# ADIS_Teensy_Arduino_Breakout_RevB.net
KiCad netlist of a schematic drawn in EAGLE
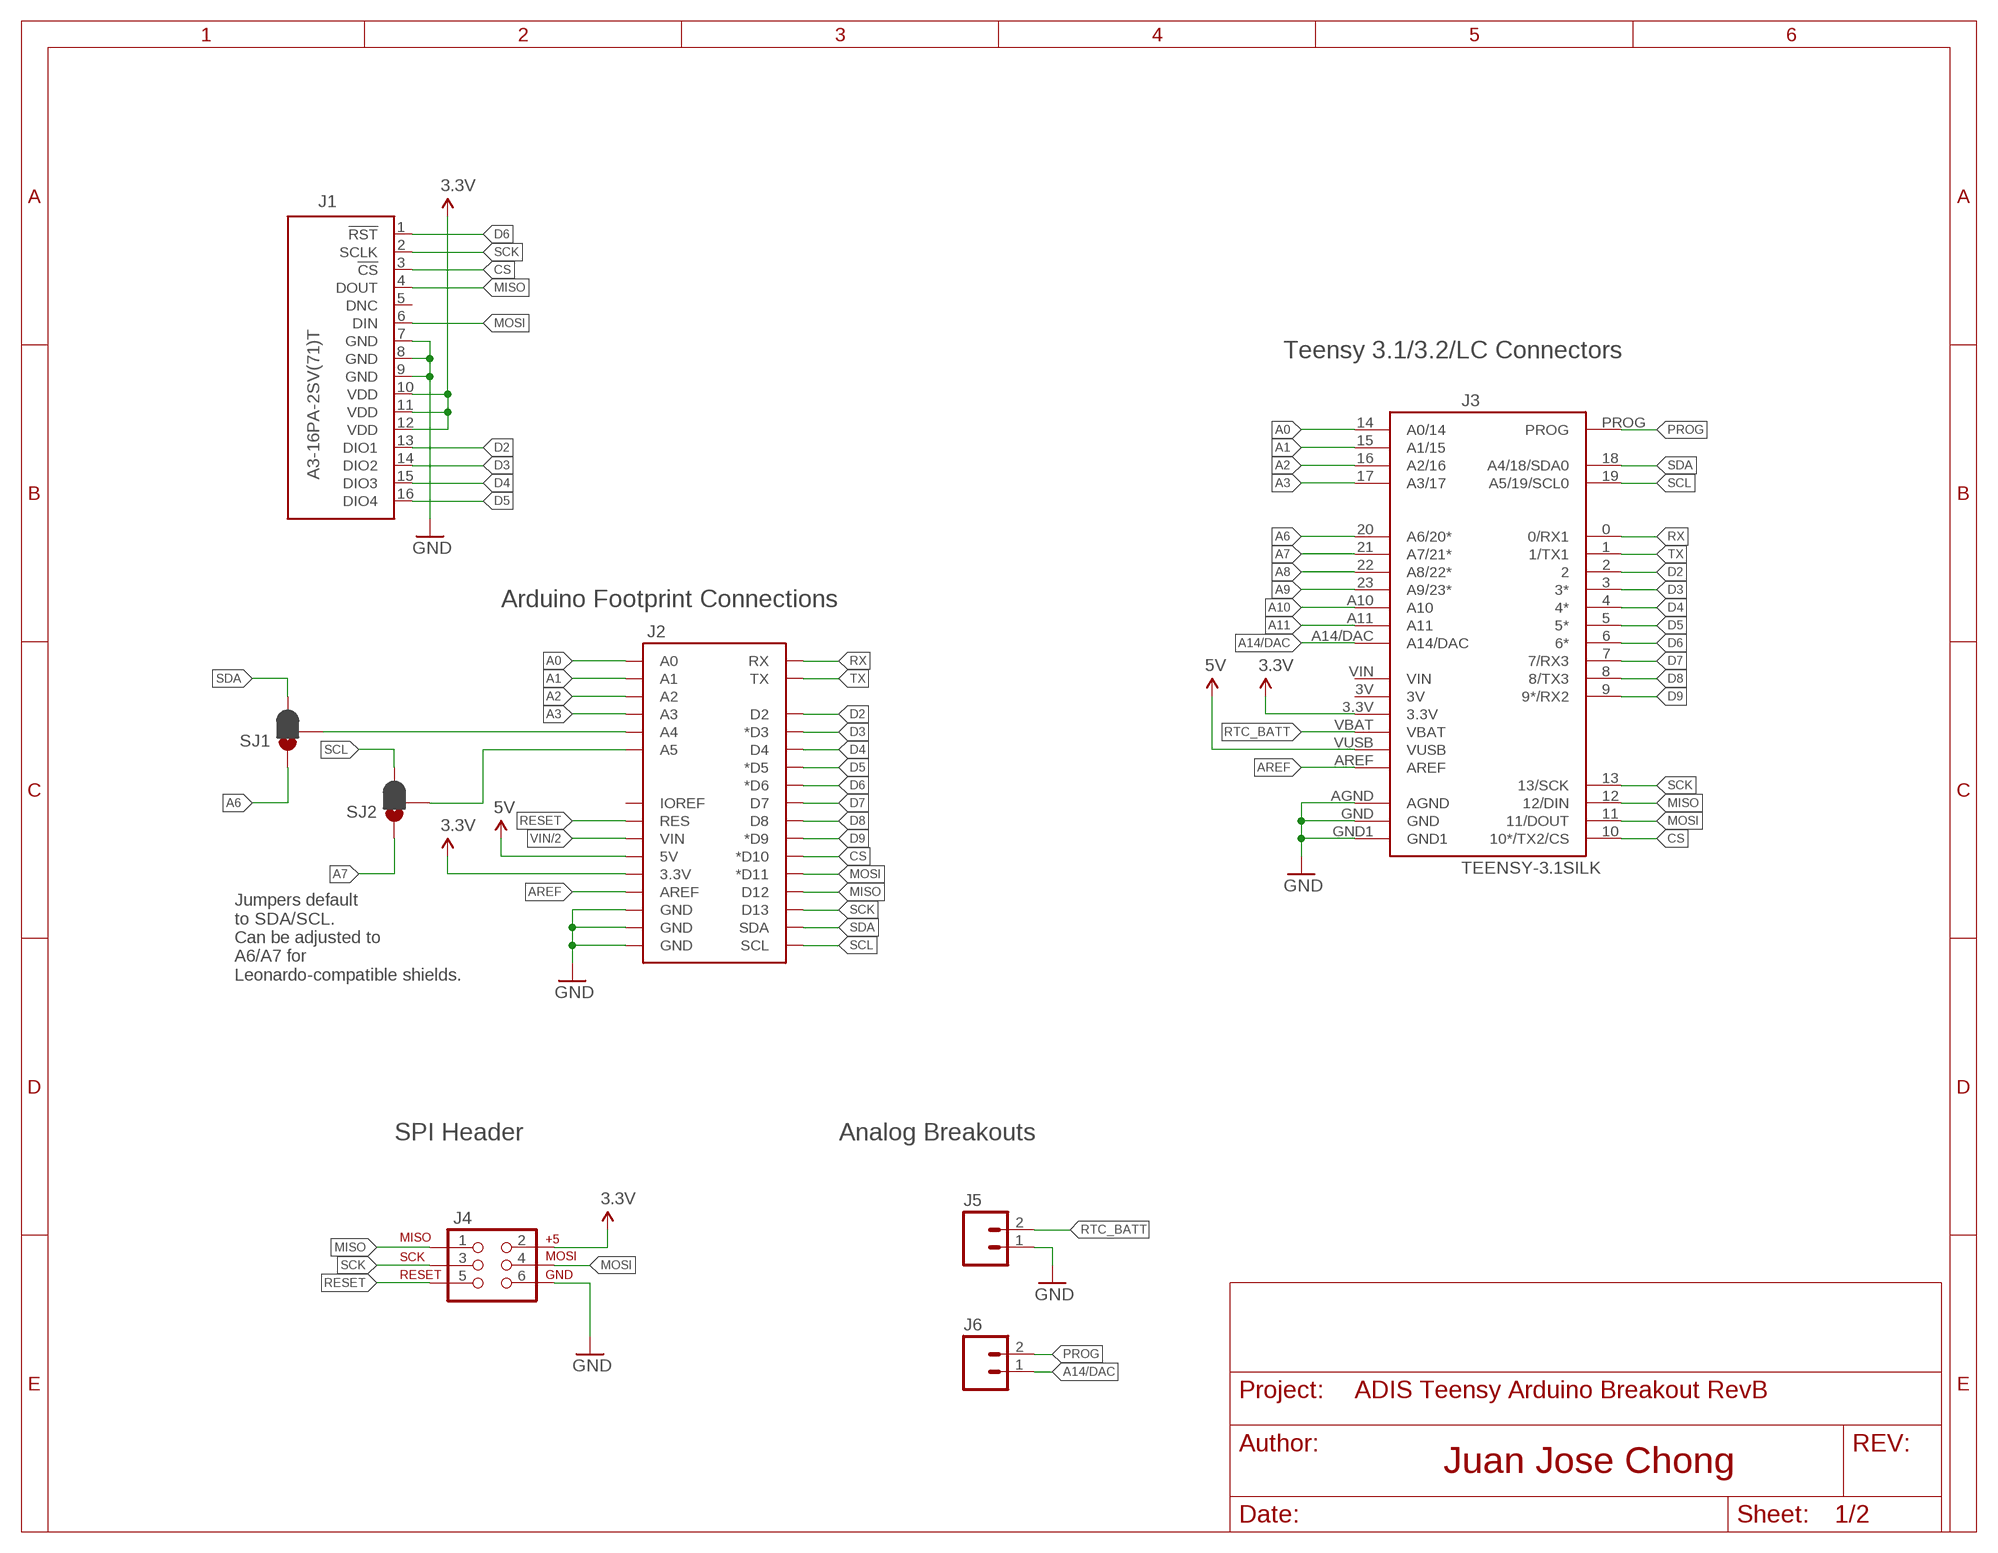
[diagram p0: schematic, sheet 1]
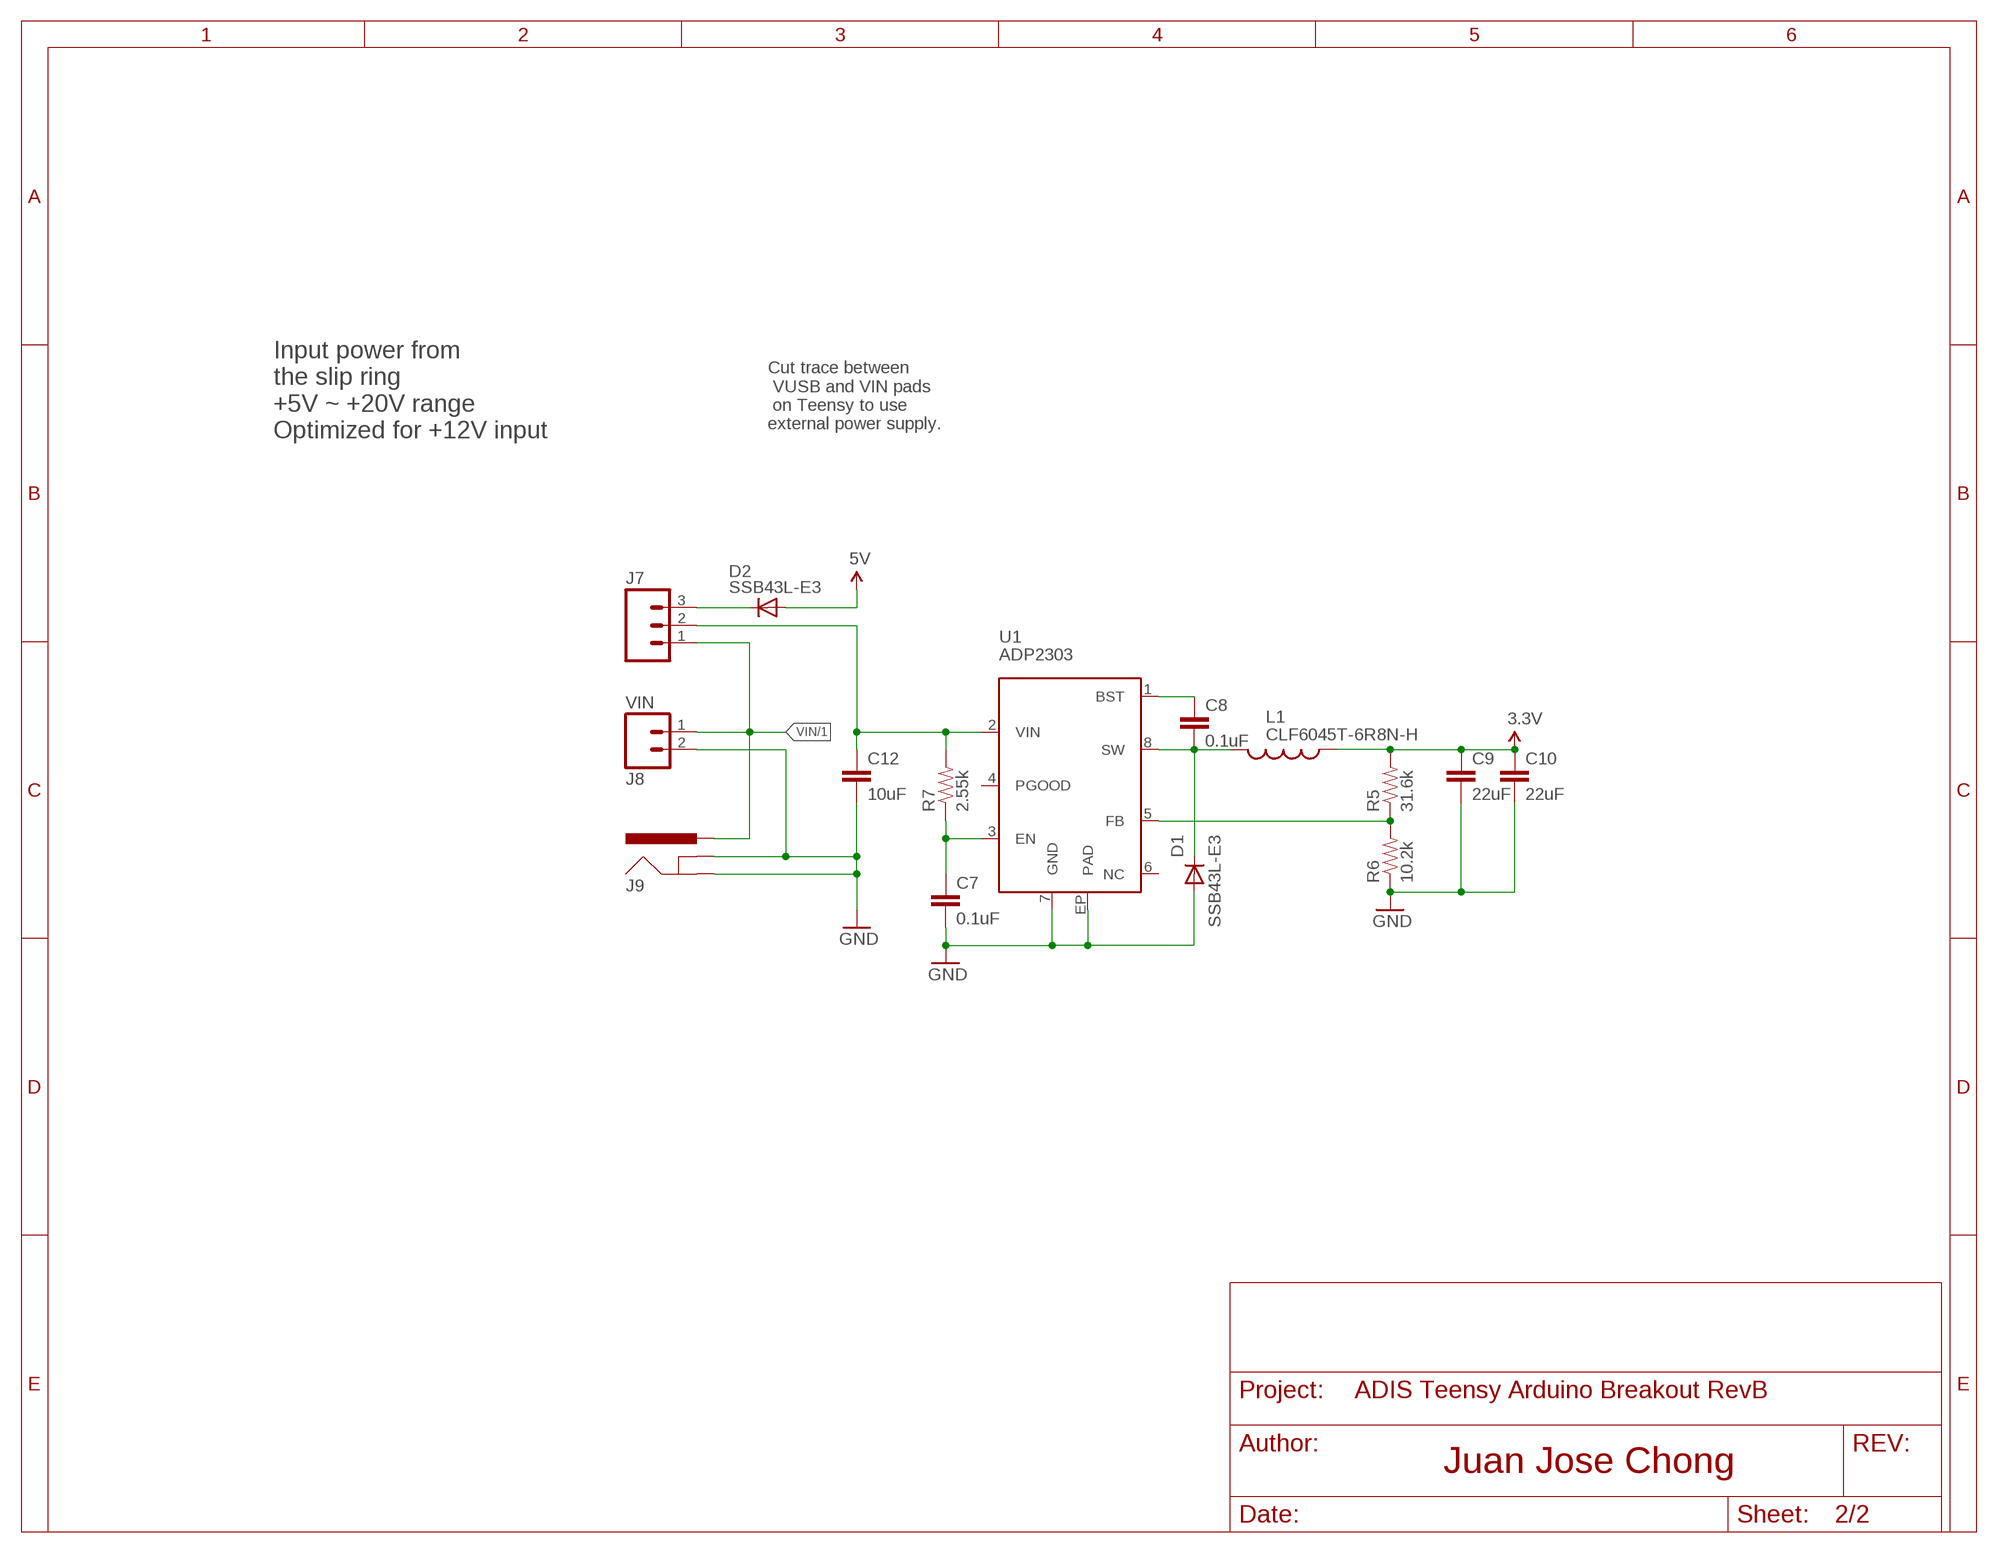
[diagram p1: schematic, sheet 2]

(export (version "E")
  (design (tool "Eeschema 10.0.6"))
  (components
    (comp (ref "C7")
      (value "0.1uF")
      (footprint "eagle-import:0603-CAP")
      (fields (field (name "PARTNO") "CL10B104KB8NNNC"))
      (libsource (lib "eagle-import") (part "CAP0603-CAP"))
    )
    (comp (ref "C8")
      (value "0.1uF")
      (footprint "eagle-import:0603-CAP")
      (fields (field (name "PARTNO") "CL10B104KB8NNNC"))
      (libsource (lib "eagle-import") (part "CAP0603-CAP"))
    )
    (comp (ref "C9")
      (value "22uF")
      (footprint "eagle-import:1210")
      (fields (field (name "PARTNO") "TLJA476M010R0600"))
      (libsource (lib "eagle-import") (part "CAP1210"))
    )
    (comp (ref "C10")
      (value "22uF")
      (footprint "eagle-import:1210")
      (fields (field (name "PARTNO") "TLJA476M010R0600"))
      (libsource (lib "eagle-import") (part "CAP1210"))
    )
    (comp (ref "C12")
      (value "10uF")
      (footprint "eagle-import:1206")
      (fields (field (name "PARTNO") "TLJA476M010R0600"))
      (libsource (lib "eagle-import") (part "CAP1206"))
    )
    (comp (ref "D1")
      (value "SSB43L-E3")
      (footprint "eagle-import:DO214AA")
      (fields (field (name "PARTNO") "SSB43L-E3/52T"))
      (libsource (lib "eagle-import") (part "DIODE-DO214AA"))
    )
    (comp (ref "D2")
      (value "SSB43L-E3")
      (footprint "eagle-import:DO214AA")
      (fields (field (name "PARTNO") "SSB43L-E3/52T"))
      (libsource (lib "eagle-import") (part "DIODE-DO214AA"))
    )
    (comp (ref "J7")
      (value "M03PTH")
      (footprint "eagle-import:1X03")
      (libsource (lib "eagle-import") (part "M03PTH"))
    )
    (comp (ref "J8")
      (value "VIN")
      (footprint "eagle-import:SCREWTERMINAL-3.5MM-2")
      (fields (field (name "PARTNO") "20020327-C021B01LF"))
      (libsource (lib "eagle-import") (part "M023.5MM"))
    )
    (comp (ref "J9")
      (value "POWER_JACKPTH_LOCK")
      (footprint "eagle-import:POWER_JACK_PTH_LOCK")
      (libsource (lib "eagle-import") (part "POWER_JACKPTH_LOCK"))
    )
    (comp (ref "L1")
      (value "CLF6045T-6R8N-H")
      (footprint "eagle-import:CLF6045-H")
      (libsource (lib "eagle-import") (part "CLF6045T-6R8N-H"))
    )
    (comp (ref "R5")
      (value "31.6k")
      (footprint "eagle-import:0603-RES")
      (fields (field (name "PARTNO") "ERJ-3EKF3162V"))
      (libsource (lib "eagle-import") (part "RESISTOR0603-RES"))
    )
    (comp (ref "R6")
      (value "10.2k")
      (footprint "eagle-import:0603-RES")
      (fields (field (name "PARTNO") "ERJ-3EKF1022V"))
      (libsource (lib "eagle-import") (part "RESISTOR0603-RES"))
    )
    (comp (ref "R7")
      (value "2.55k")
      (footprint "eagle-import:0603-RES")
      (fields (field (name "PARTNO") "ERJ-3EKF2551V"))
      (libsource (lib "eagle-import") (part "RESISTOR0603-RES"))
    )
    (comp (ref "U1")
      (value "ADP2303")
      (footprint "eagle-import:SOIC-8-PAD")
      (fields (field (name "PARTNO") "ADP2303ARDZ"))
      (libsource (lib "eagle-import") (part "ADP2303"))
    )
    (comp (ref "J1")
      (value "A3-16PA-2SV(71)T")
      (footprint "eagle-import:A3-16PA-2SV(71)-TOP")
      (libsource (lib "eagle-import") (part "A3-16PA-2SV(71)T"))
    )
    (comp (ref "J2")
      (value "ARDUINO_R3_SHIELDUNO_R3_SHIELD_HOLES")
      (footprint "eagle-import:UNO_R3_SHIELD_HOLES")
      (libsource (lib "eagle-import") (part "ARDUINO_R3_SHIELDUNO_R3_SHIELD_HOLES"))
    )
    (comp (ref "J3")
      (value "TEENSY-3.1SILK")
      (footprint "eagle-import:TEENSY-3.1")
      (libsource (lib "eagle-import") (part "TEENSY-3.1SILK"))
    )
    (comp (ref "J4")
      (value "AVR_SPI_PRG_6PTH")
      (footprint "eagle-import:2X3")
      (libsource (lib "eagle-import") (part "AVR_SPI_PRG_6PTH"))
    )
    (comp (ref "J5")
      (value "M02PTH")
      (footprint "eagle-import:1X02")
      (libsource (lib "eagle-import") (part "M02PTH"))
    )
    (comp (ref "J6")
      (value "M02PTH")
      (footprint "eagle-import:1X02")
      (libsource (lib "eagle-import") (part "M02PTH"))
    )
    (comp (ref "SJ1")
      (value "JUMPER-PAD-3-2OF3_NC_BY_PASTE")
      (footprint "eagle-import:PAD-JUMPER-3-2OF3_NC_BY_PASTE_YES_SILK_FULL_BOX")
      (libsource (lib "eagle-import") (part "JUMPER-PAD-3-2OF3_NC_BY_PASTE"))
    )
    (comp (ref "SJ2")
      (value "JUMPER-PAD-3-2OF3_NC_BY_PASTE")
      (footprint "eagle-import:PAD-JUMPER-3-2OF3_NC_BY_PASTE_YES_SILK_FULL_BOX")
      (libsource (lib "eagle-import") (part "JUMPER-PAD-3-2OF3_NC_BY_PASTE"))
    )
  )
  (nets
    (net (code "1") (name "3.3V") (class "Default")
      (node (ref "C10") (pin "1") (pinfunction "1_1") (pintype "passive"))
      (node (ref "C9") (pin "1") (pinfunction "1_1") (pintype "passive"))
      (node (ref "J1") (pin "10") (pinfunction "VDD_10") (pintype "bidirectional"))
      (node (ref "J1") (pin "11") (pinfunction "VDD_11") (pintype "bidirectional"))
      (node (ref "J1") (pin "12") (pinfunction "VDD_12") (pintype "bidirectional"))
      (node (ref "J2") (pin "3.3V") (pinfunction "3.3V_3.3V") (pintype "bidirectional"))
      (node (ref "J3") (pin "3.3V") (pinfunction "3.3V_3.3V") (pintype "bidirectional"))
      (node (ref "J4") (pin "2") (pinfunction "2_2") (pintype "passive"))
      (node (ref "L1") (pin "P$1") (pinfunction "1_P$1") (pintype "passive"))
      (node (ref "R5") (pin "2") (pinfunction "2_2") (pintype "passive"))
    )
    (net (code "2") (name "5V") (class "Default")
      (node (ref "D2") (pin "A") (pinfunction "A_A") (pintype "passive"))
      (node (ref "J2") (pin "5V") (pinfunction "5V_5V") (pintype "bidirectional"))
      (node (ref "J3") (pin "VUSB") (pinfunction "VUSB_VUSB") (pintype "bidirectional"))
    )
    (net (code "3") (name "A0") (class "Default")
      (node (ref "J2") (pin "A0") (pinfunction "A0_A0") (pintype "bidirectional"))
      (node (ref "J3") (pin "14") (pinfunction "A0/14_14") (pintype "bidirectional"))
    )
    (net (code "4") (name "A1") (class "Default")
      (node (ref "J2") (pin "A1") (pinfunction "A1_A1") (pintype "bidirectional"))
      (node (ref "J3") (pin "15") (pinfunction "A1/15_15") (pintype "bidirectional"))
    )
    (net (code "5") (name "A2") (class "Default")
      (node (ref "J2") (pin "A2") (pinfunction "A2_A2") (pintype "bidirectional"))
      (node (ref "J3") (pin "16") (pinfunction "A2/16_16") (pintype "bidirectional"))
    )
    (net (code "6") (name "A3") (class "Default")
      (node (ref "J2") (pin "A3") (pinfunction "A3_A3") (pintype "bidirectional"))
      (node (ref "J3") (pin "17") (pinfunction "A3/17_17") (pintype "bidirectional"))
    )
    (net (code "7") (name "A6") (class "Default")
      (node (ref "J3") (pin "20") (pinfunction "A6/20*_20") (pintype "bidirectional"))
      (node (ref "SJ1") (pin "1") (pinfunction "1_1") (pintype "passive"))
    )
    (net (code "8") (name "A7") (class "Default")
      (node (ref "J3") (pin "21") (pinfunction "A7/21*_21") (pintype "bidirectional"))
      (node (ref "SJ2") (pin "1") (pinfunction "1_1") (pintype "passive"))
    )
    (net (code "9") (name "A8") (class "Default")
      (node (ref "J3") (pin "22") (pinfunction "A8/22*_22") (pintype "bidirectional"))
    )
    (net (code "10") (name "A9") (class "Default")
      (node (ref "J3") (pin "23") (pinfunction "A9/23*_23") (pintype "bidirectional"))
    )
    (net (code "11") (name "A10") (class "Default")
      (node (ref "J3") (pin "A10") (pinfunction "A10_A10") (pintype "bidirectional"))
    )
    (net (code "12") (name "A11") (class "Default")
      (node (ref "J3") (pin "A11") (pinfunction "A11_A11") (pintype "bidirectional"))
    )
    (net (code "13") (name "A14{slash}DAC") (class "Default")
      (node (ref "J3") (pin "A14/DAC") (pinfunction "A14/DAC_A14/DAC") (pintype "bidirectional"))
      (node (ref "J6") (pin "1") (pinfunction "1_1") (pintype "passive"))
    )
    (net (code "14") (name "AREF") (class "Default")
      (node (ref "J2") (pin "AREF") (pinfunction "AREF_AREF") (pintype "bidirectional"))
      (node (ref "J3") (pin "AREF") (pinfunction "AREF_AREF") (pintype "bidirectional"))
    )
    (net (code "15") (name "CS") (class "Default")
      (node (ref "J1") (pin "3") (pinfunction "~{CS}_3") (pintype "bidirectional"))
      (node (ref "J2") (pin "D10") (pinfunction "*D10_D10") (pintype "bidirectional"))
      (node (ref "J3") (pin "10") (pinfunction "10*/TX2/CS_10") (pintype "bidirectional"))
    )
    (net (code "16") (name "D2") (class "Default")
      (node (ref "J1") (pin "13") (pinfunction "DIO1_13") (pintype "bidirectional"))
      (node (ref "J2") (pin "D2") (pinfunction "D2_D2") (pintype "bidirectional"))
      (node (ref "J3") (pin "2") (pinfunction "2_2") (pintype "bidirectional"))
    )
    (net (code "17") (name "D3") (class "Default")
      (node (ref "J1") (pin "14") (pinfunction "DIO2_14") (pintype "bidirectional"))
      (node (ref "J2") (pin "D3") (pinfunction "*D3_D3") (pintype "bidirectional"))
      (node (ref "J3") (pin "3") (pinfunction "3*_3") (pintype "bidirectional"))
    )
    (net (code "18") (name "D4") (class "Default")
      (node (ref "J1") (pin "15") (pinfunction "DIO3_15") (pintype "bidirectional"))
      (node (ref "J2") (pin "D4") (pinfunction "D4_D4") (pintype "bidirectional"))
      (node (ref "J3") (pin "4") (pinfunction "4*_4") (pintype "bidirectional"))
    )
    (net (code "19") (name "D5") (class "Default")
      (node (ref "J1") (pin "16") (pinfunction "DIO4_16") (pintype "bidirectional"))
      (node (ref "J2") (pin "D5") (pinfunction "*D5_D5") (pintype "bidirectional"))
      (node (ref "J3") (pin "5") (pinfunction "5*_5") (pintype "bidirectional"))
    )
    (net (code "20") (name "D6") (class "Default")
      (node (ref "J1") (pin "1") (pinfunction "~{RST}_1") (pintype "bidirectional"))
      (node (ref "J2") (pin "D6") (pinfunction "*D6_D6") (pintype "bidirectional"))
      (node (ref "J3") (pin "6") (pinfunction "6*_6") (pintype "bidirectional"))
    )
    (net (code "21") (name "D7") (class "Default")
      (node (ref "J2") (pin "D7") (pinfunction "D7_D7") (pintype "bidirectional"))
      (node (ref "J3") (pin "7") (pinfunction "7/RX3_7") (pintype "bidirectional"))
    )
    (net (code "22") (name "D8") (class "Default")
      (node (ref "J2") (pin "D8") (pinfunction "D8_D8") (pintype "bidirectional"))
      (node (ref "J3") (pin "8") (pinfunction "8/TX3_8") (pintype "bidirectional"))
    )
    (net (code "23") (name "D9") (class "Default")
      (node (ref "J2") (pin "D9") (pinfunction "*D9_D9") (pintype "bidirectional"))
      (node (ref "J3") (pin "9") (pinfunction "9*/RX2_9") (pintype "bidirectional"))
    )
    (net (code "24") (name "GND") (class "Default")
      (node (ref "C10") (pin "2") (pinfunction "2_2") (pintype "passive"))
      (node (ref "C12") (pin "2") (pinfunction "2_2") (pintype "passive"))
      (node (ref "C7") (pin "2") (pinfunction "2_2") (pintype "passive"))
      (node (ref "C9") (pin "2") (pinfunction "2_2") (pintype "passive"))
      (node (ref "D1") (pin "A") (pinfunction "A_A") (pintype "passive"))
      (node (ref "J1") (pin "7") (pinfunction "GND_7") (pintype "bidirectional"))
      (node (ref "J1") (pin "8") (pinfunction "GND_8") (pintype "bidirectional"))
      (node (ref "J1") (pin "9") (pinfunction "GND_9") (pintype "bidirectional"))
      (node (ref "J2") (pin "GND@0") (pinfunction "GND_GND@0") (pintype "bidirectional"))
      (node (ref "J2") (pin "GND@1") (pinfunction "GND_GND@1") (pintype "bidirectional"))
      (node (ref "J2") (pin "GND@2") (pinfunction "GND_GND@2") (pintype "bidirectional"))
      (node (ref "J3") (pin "AGND") (pinfunction "AGND_AGND") (pintype "bidirectional"))
      (node (ref "J3") (pin "GND") (pinfunction "GND_GND") (pintype "bidirectional"))
      (node (ref "J3") (pin "GND1") (pinfunction "GND1_GND1") (pintype "bidirectional"))
      (node (ref "J4") (pin "6") (pinfunction "6_6") (pintype "passive"))
      (node (ref "J5") (pin "1") (pinfunction "1_1") (pintype "passive"))
      (node (ref "J8") (pin "2") (pinfunction "2_2") (pintype "passive"))
      (node (ref "J9") (pin "GND") (pinfunction "GND_GND") (pintype "bidirectional"))
      (node (ref "J9") (pin "GNDBREAK") (pinfunction "GNDBREAK_GNDBREAK") (pintype "bidirectional"))
      (node (ref "R6") (pin "1") (pinfunction "1_1") (pintype "passive"))
      (node (ref "U1") (pin "7") (pinfunction "GND_7") (pintype "bidirectional"))
      (node (ref "U1") (pin "EP") (pinfunction "PAD_EP") (pintype "bidirectional"))
    )
    (net (code "25") (name "MISO") (class "Default")
      (node (ref "J1") (pin "4") (pinfunction "DOUT_4") (pintype "bidirectional"))
      (node (ref "J2") (pin "D12") (pinfunction "D12_D12") (pintype "bidirectional"))
      (node (ref "J3") (pin "12") (pinfunction "12/DIN_12") (pintype "bidirectional"))
      (node (ref "J4") (pin "1") (pinfunction "1_1") (pintype "passive"))
    )
    (net (code "26") (name "MOSI") (class "Default")
      (node (ref "J1") (pin "6") (pinfunction "DIN_6") (pintype "bidirectional"))
      (node (ref "J2") (pin "D11") (pinfunction "*D11_D11") (pintype "bidirectional"))
      (node (ref "J3") (pin "11") (pinfunction "11/DOUT_11") (pintype "bidirectional"))
      (node (ref "J4") (pin "4") (pinfunction "4_4") (pintype "passive"))
    )
    (net (code "27") (name "Net-(D2-PadC)") (class "Default")
      (node (ref "D2") (pin "C") (pinfunction "C_C") (pintype "passive"))
      (node (ref "J7") (pin "3") (pinfunction "3_3") (pintype "passive"))
    )
    (net (code "28") (name "Net-(J2-PadA4)") (class "Default")
      (node (ref "J2") (pin "A4") (pinfunction "A4_A4") (pintype "bidirectional"))
      (node (ref "SJ1") (pin "2") (pinfunction "2_2") (pintype "passive"))
    )
    (net (code "29") (name "Net-(J2-PadA5)") (class "Default")
      (node (ref "J2") (pin "A5") (pinfunction "A5_A5") (pintype "bidirectional"))
      (node (ref "SJ2") (pin "2") (pinfunction "2_2") (pintype "passive"))
    )
    (net (code "30") (name "Net-(L1-2)") (class "Default")
      (node (ref "C8") (pin "2") (pinfunction "2_2") (pintype "passive"))
      (node (ref "D1") (pin "C") (pinfunction "C_C") (pintype "passive"))
      (node (ref "L1") (pin "P$2") (pinfunction "2_P$2") (pintype "passive"))
      (node (ref "U1") (pin "8") (pinfunction "SW_8") (pintype "bidirectional"))
    )
    (net (code "31") (name "Net-(U1-BST)") (class "Default")
      (node (ref "C8") (pin "1") (pinfunction "1_1") (pintype "passive"))
      (node (ref "U1") (pin "1") (pinfunction "BST_1") (pintype "bidirectional"))
    )
    (net (code "32") (name "Net-(U1-EN)") (class "Default")
      (node (ref "C7") (pin "1") (pinfunction "1_1") (pintype "passive"))
      (node (ref "R7") (pin "1") (pinfunction "1_1") (pintype "passive"))
      (node (ref "U1") (pin "3") (pinfunction "EN_3") (pintype "bidirectional"))
    )
    (net (code "33") (name "Net-(U1-FB)") (class "Default")
      (node (ref "R5") (pin "1") (pinfunction "1_1") (pintype "passive"))
      (node (ref "R6") (pin "2") (pinfunction "2_2") (pintype "passive"))
      (node (ref "U1") (pin "5") (pinfunction "FB_5") (pintype "bidirectional"))
    )
    (net (code "34") (name "Net-(U1-VIN)") (class "Default")
      (node (ref "C12") (pin "1") (pinfunction "1_1") (pintype "passive"))
      (node (ref "J7") (pin "2") (pinfunction "2_2") (pintype "passive"))
      (node (ref "R7") (pin "2") (pinfunction "2_2") (pintype "passive"))
      (node (ref "U1") (pin "2") (pinfunction "VIN_2") (pintype "bidirectional"))
    )
    (net (code "35") (name "PROG") (class "Default")
      (node (ref "J3") (pin "PROG") (pinfunction "PROG_PROG") (pintype "bidirectional"))
      (node (ref "J6") (pin "2") (pinfunction "2_2") (pintype "passive"))
    )
    (net (code "36") (name "RESET") (class "Default")
      (node (ref "J2") (pin "RES") (pinfunction "RES_RES") (pintype "bidirectional"))
      (node (ref "J4") (pin "5") (pinfunction "5_5") (pintype "passive"))
    )
    (net (code "37") (name "RTC_BATT") (class "Default")
      (node (ref "J3") (pin "VBAT") (pinfunction "VBAT_VBAT") (pintype "bidirectional"))
      (node (ref "J5") (pin "2") (pinfunction "2_2") (pintype "passive"))
    )
    (net (code "38") (name "RX") (class "Default")
      (node (ref "J2") (pin "RX") (pinfunction "RX_RX") (pintype "bidirectional"))
      (node (ref "J3") (pin "0") (pinfunction "0/RX1_0") (pintype "bidirectional"))
    )
    (net (code "39") (name "SCK") (class "Default")
      (node (ref "J1") (pin "2") (pinfunction "SCLK_2") (pintype "bidirectional"))
      (node (ref "J2") (pin "D13") (pinfunction "D13_D13") (pintype "bidirectional"))
      (node (ref "J3") (pin "13") (pinfunction "13/SCK_13") (pintype "bidirectional"))
      (node (ref "J4") (pin "3") (pinfunction "3_3") (pintype "passive"))
    )
    (net (code "40") (name "SCL") (class "Default")
      (node (ref "J2") (pin "SCL") (pinfunction "SCL_SCL") (pintype "bidirectional"))
      (node (ref "J3") (pin "19") (pinfunction "A5/19/SCL0_19") (pintype "bidirectional"))
      (node (ref "SJ2") (pin "3") (pinfunction "3_3") (pintype "passive"))
    )
    (net (code "41") (name "SDA") (class "Default")
      (node (ref "J2") (pin "SDA") (pinfunction "SDA_SDA") (pintype "bidirectional"))
      (node (ref "J3") (pin "18") (pinfunction "A4/18/SDA0_18") (pintype "bidirectional"))
      (node (ref "SJ1") (pin "3") (pinfunction "3_3") (pintype "passive"))
    )
    (net (code "42") (name "TX") (class "Default")
      (node (ref "J2") (pin "TX") (pinfunction "TX_TX") (pintype "bidirectional"))
      (node (ref "J3") (pin "1") (pinfunction "1/TX1_1") (pintype "bidirectional"))
    )
    (net (code "43") (name "VIN") (class "Default")
      (node (ref "J2") (pin "VIN") (pinfunction "VIN_VIN") (pintype "bidirectional"))
      (node (ref "J7") (pin "1") (pinfunction "1_1") (pintype "passive"))
      (node (ref "J8") (pin "1") (pinfunction "1_1") (pintype "passive"))
      (node (ref "J9") (pin "PWR") (pinfunction "PWR_PWR") (pintype "bidirectional"))
    )
    (net (code "44") (name "unconnected-(J1-DNC-Pad5)") (class "Default")
      (node (ref "J1") (pin "5") (pinfunction "DNC_5") (pintype "bidirectional"))
    )
    (net (code "45") (name "unconnected-(J2-PadIOREF)") (class "Default")
      (node (ref "J2") (pin "IOREF") (pinfunction "IOREF_IOREF") (pintype "bidirectional"))
    )
    (net (code "46") (name "unconnected-(J3-Pad3V)") (class "Default")
      (node (ref "J3") (pin "3V") (pinfunction "3V_3V") (pintype "bidirectional"))
    )
    (net (code "47") (name "unconnected-(J3-PadVIN)") (class "Default")
      (node (ref "J3") (pin "VIN") (pinfunction "VIN_VIN") (pintype "bidirectional"))
    )
    (net (code "48") (name "unconnected-(U1-NC-Pad6)") (class "Default")
      (node (ref "U1") (pin "6") (pinfunction "NC_6") (pintype "bidirectional"))
    )
    (net (code "49") (name "unconnected-(U1-PGOOD-Pad4)") (class "Default")
      (node (ref "U1") (pin "4") (pinfunction "PGOOD_4") (pintype "bidirectional"))
    )
  )
)
